# RTC.net
KiCad netlist of a schematic drawn in Altium Designer
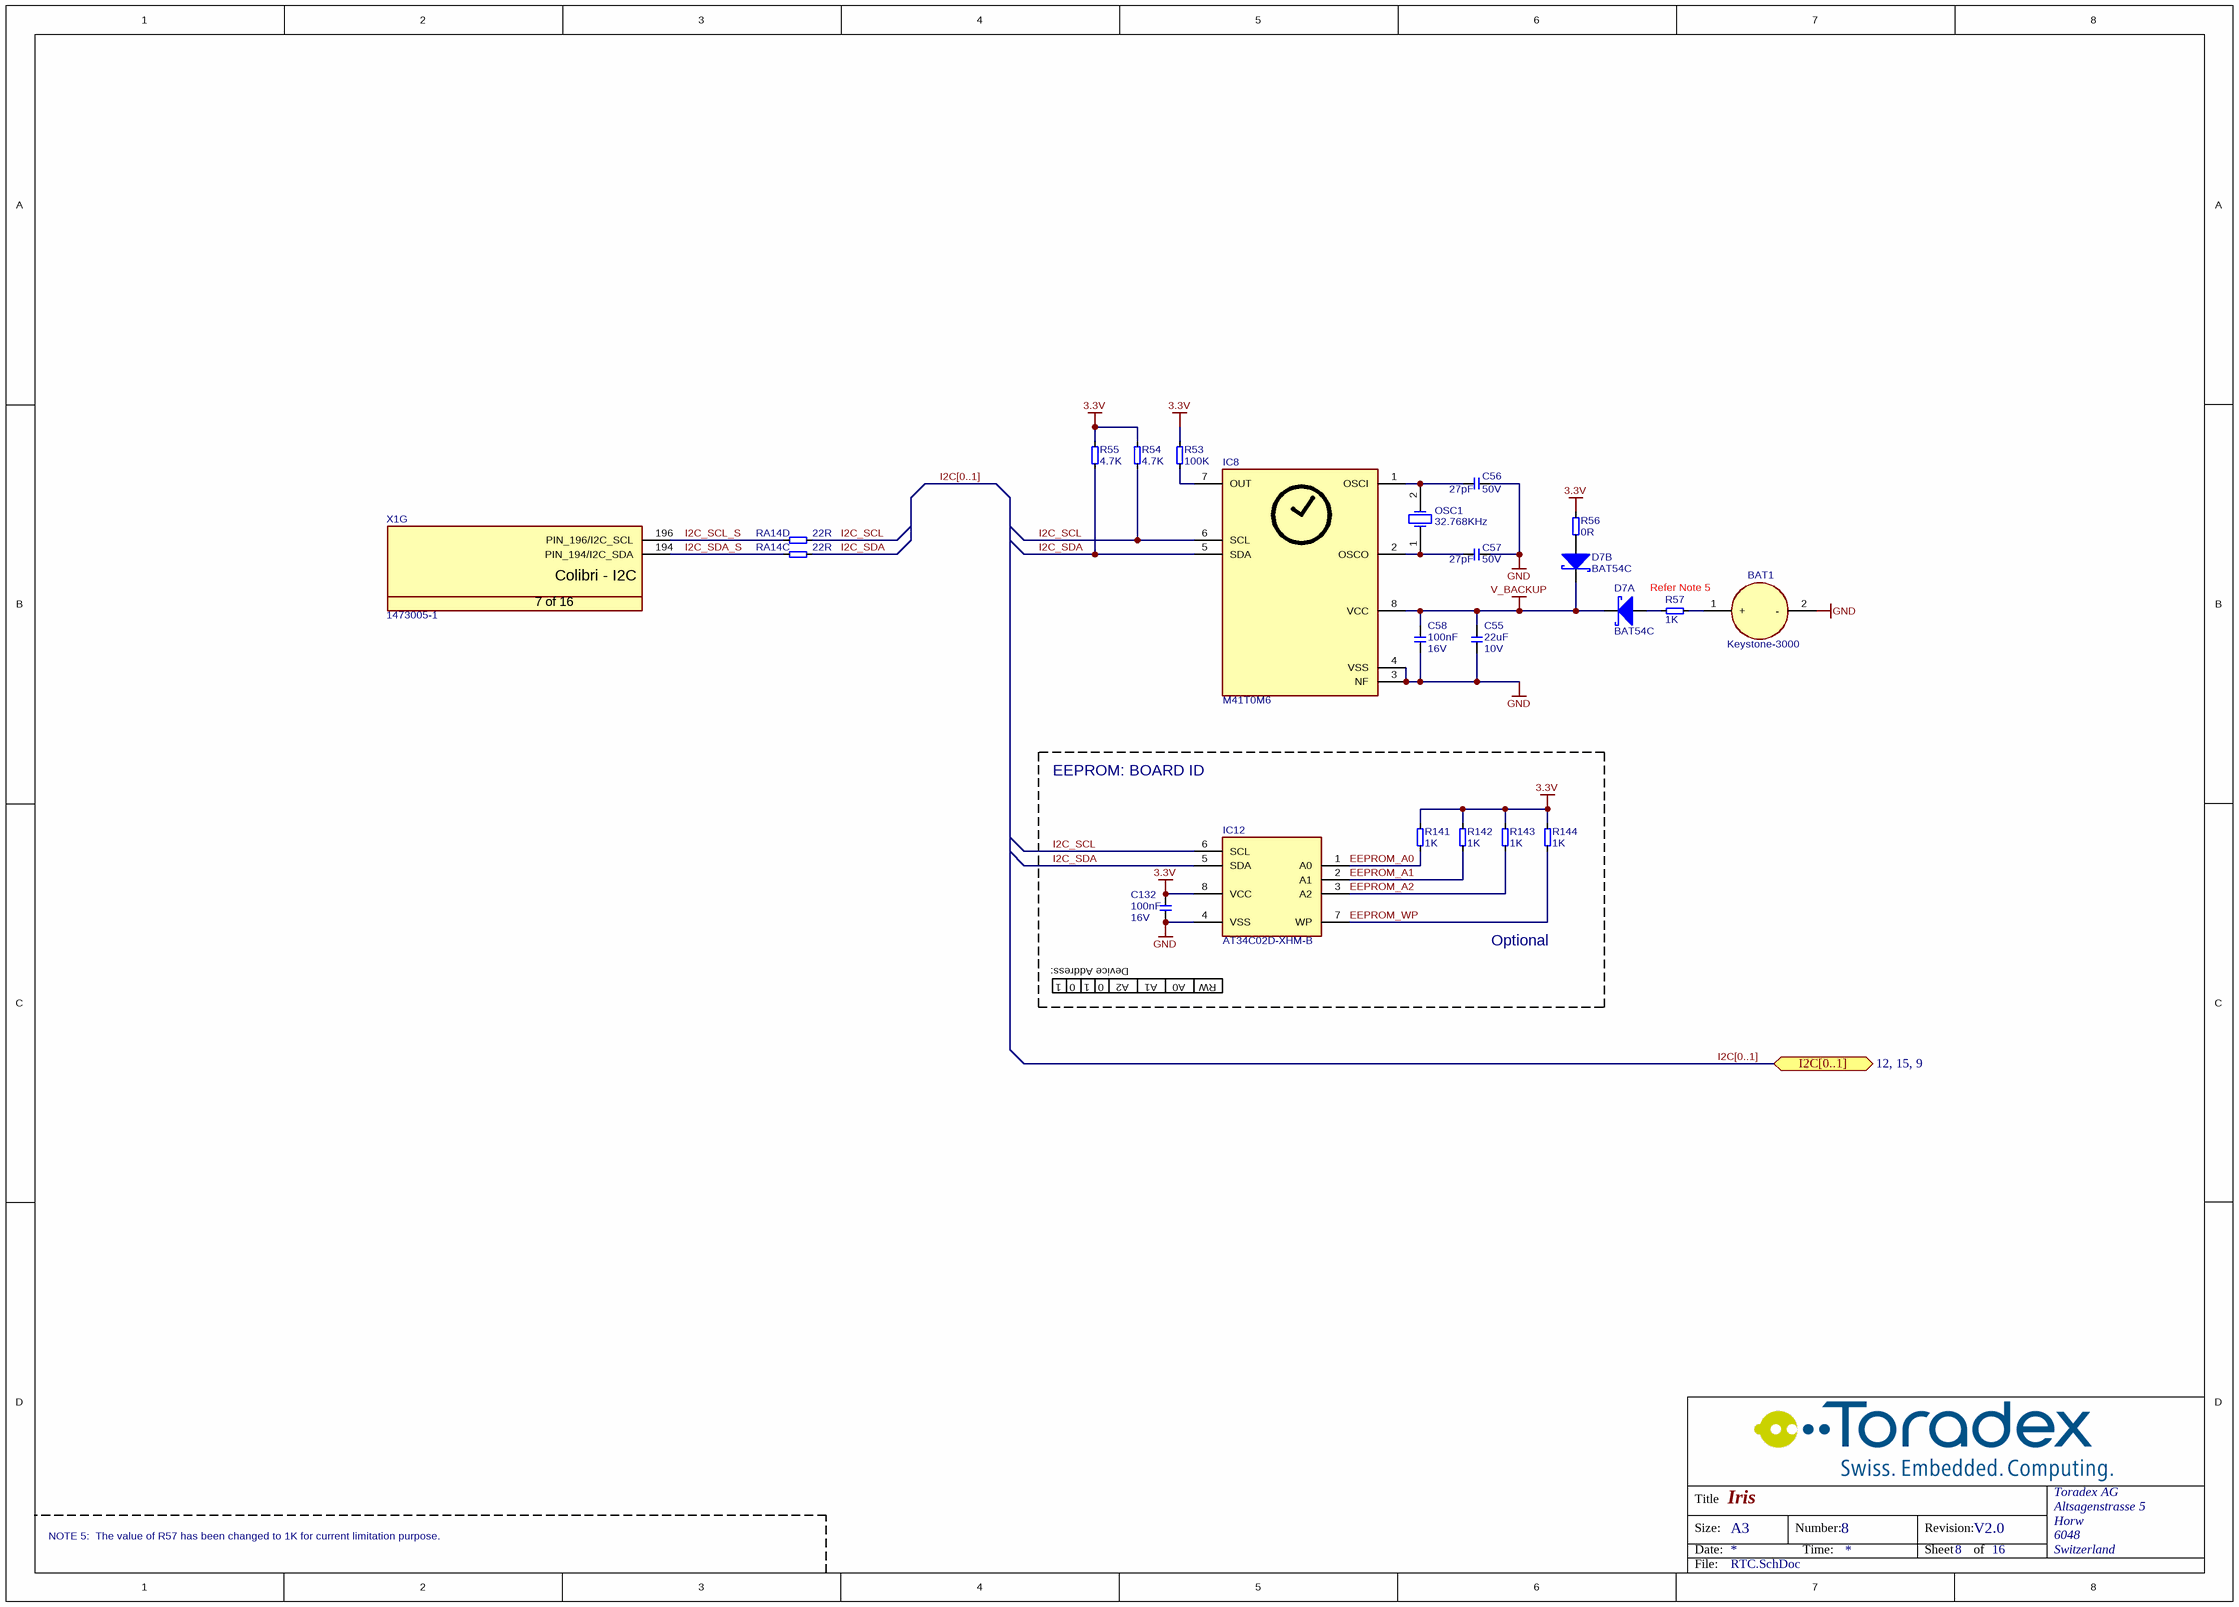
[diagram p0: RTC.SchDoc]

(export (version "E")
  (design (tool "Eeschema 10.0.6"))
  (components
    (comp (ref "BAT1")
      (value "Keystone-3000")
      (footprint "T_Keystone_3000")
      (description "Battery Holder")
      (fields (field (name "MANUFACTURER PART NO.") "3000"))
      (libsource (lib "Iris") (part "BAT-Keystone-3000"))
    )
    (comp (ref "C55")
      (value "22uF")
      (footprint "T_CAPC0805X125N")
      (description "Capacitor Ceramic X5R 22uF 10V 20% 0805")
      (fields (field (name "TOLERANCE") "20%") (field (name "RATING") "10V"))
      (libsource (lib "Iris") (part "C-X5R-22uF-10V-20%-0805"))
    )
    (comp (ref "C56")
      (value "27pF")
      (footprint "T_CAPC0603X33N")
      (description "Capacitor Ceramic NPO 27pF 50V 5% 0603")
      (fields (field (name "TOLERANCE") "5%") (field (name "RATING") "50V"))
      (libsource (lib "Iris") (part "C-NPO-27pF-50V-5%-0603"))
    )
    (comp (ref "C57")
      (value "27pF")
      (footprint "T_CAPC0603X33N")
      (description "Capacitor Ceramic NPO 27pF 50V 5% 0603")
      (fields (field (name "TOLERANCE") "5%") (field (name "RATING") "50V"))
      (libsource (lib "Iris") (part "C-NPO-27pF-50V-5%-0603"))
    )
    (comp (ref "C58")
      (value "100nF")
      (footprint "CAPC1005X60N")
      (description "Capacitor Ceramic X7R 100nF 16V 10% 0402")
      (fields (field (name "TOLERANCE") "10%") (field (name "RATING") "16V"))
      (libsource (lib "Iris") (part "C-X7R-100nF-16V-10%-0402"))
    )
    (comp (ref "C132")
      (value "100nF")
      (footprint "CAPC1005X60N")
      (description "Capacitor Ceramic X7R 100nF 16V 10% 0402")
      (fields (field (name "TOLERANCE") "10%") (field (name "RATING") "16V"))
      (libsource (lib "Iris") (part "C-X7R-100nF-16V-10%-0402"))
    )
    (comp (ref "D7")
      (value "BAT54C")
      (footprint "SOT95P230X110-3N")
      (description "BAT54C Schottky Diode")
      (fields (field (name "MANUFACTURER PART NO.") "BAT54C"))
      (libsource (lib "Iris") (part "D-Philips-BAT54C-Schottky"))
    )
    (comp (ref "IC8")
      (value "M41T0M6")
      (footprint "SOIC127P600X173-8N")
      (description "RTC M41T0M6")
      (fields (field (name "MANUFACTURER PART NO.") "M41T0M6"))
      (libsource (lib "Iris") (part "IC-ST-M41T0M6"))
    )
    (comp (ref "IC12")
      (value "AT34C02D-XHM-B")
      (footprint "TSOP65P650X120-8M")
      (description "EEPROM, 2Kbit (256 x 8), TSSOP-8 package")
      (fields (field (name "MANUFACTURER PART NO.") "AT34C02D-XHM-B"))
      (libsource (lib "Iris") (part "IC-Microchip-AT34C02D-XHM-B"))
    )
    (comp (ref "OSC1")
      (value "32.768KHz")
      (footprint "T_MC_CC4V-T1A")
      (description "Quartz 32.768kHz")
      (fields (field (name "TOLERANCE") "30ppm") (field (name "MANUFACTURER PART NO.") "CC4V-T1A"))
      (libsource (lib "Iris") (part "OSC-MC-CC4V-T1A-32.768KHz-30ppm-5x1.9mm"))
    )
    (comp (ref "R53")
      (value "100K")
      (footprint "T_RESC0603X30N")
      (description "Resistor 100 Kohm 63mW 5% 0603")
      (fields (field (name "TOLERANCE") "5%"))
      (libsource (lib "Iris") (part "R-100KR-63mW-5%-0603"))
    )
    (comp (ref "R54")
      (value "4.7K")
      (footprint "RESC1005X40N")
      (description "Resistor 4.7 Kohm 63mW 5% 0402")
      (fields (field (name "TOLERANCE") "5%"))
      (libsource (lib "Iris") (part "R-4.7kR-63mW-5%-0402"))
    )
    (comp (ref "R55")
      (value "4.7K")
      (footprint "RESC1005X40N")
      (description "Resistor 4.7 Kohm 63mW 5% 0402")
      (fields (field (name "TOLERANCE") "5%"))
      (libsource (lib "Iris") (part "R-4.7kR-63mW-5%-0402"))
    )
    (comp (ref "R56")
      (value "0R")
      (footprint "T_RESC0603X30N")
      (description "Resistor 0 ohm 63mW 5% 0603")
      (fields (field (name "TOLERANCE") "5%"))
      (libsource (lib "Iris") (part "R-0R-63mW-5%-0603"))
    )
    (comp (ref "R57")
      (value "1K")
      (footprint "RESC1005X40N")
      (description "Resistor 1 Kohm 63mW 5% 0402")
      (fields (field (name "TOLERANCE") "5%"))
      (libsource (lib "Iris") (part "R-1KR-63mW-5%-0402"))
    )
    (comp (ref "R141")
      (value "1K")
      (footprint "T_RESC0603X30N")
      (description "Resistor 1 Kohm 63mW 5% 0603")
      (fields (field (name "TOLERANCE") "5%"))
      (libsource (lib "Iris") (part "R-1KR-63mW-5%-0603"))
    )
    (comp (ref "R142")
      (value "1K")
      (footprint "T_RESC0603X30N")
      (description "Resistor 1 Kohm 63mW 5% 0603")
      (fields (field (name "TOLERANCE") "5%"))
      (libsource (lib "Iris") (part "R-1KR-63mW-5%-0603"))
    )
    (comp (ref "R143")
      (value "1K")
      (footprint "T_RESC0603X30N")
      (description "Resistor 1 Kohm 63mW 5% 0603")
      (fields (field (name "TOLERANCE") "5%"))
      (libsource (lib "Iris") (part "R-1KR-63mW-5%-0603"))
    )
    (comp (ref "R144")
      (value "1K")
      (footprint "T_RESC0603X30N")
      (description "Resistor 1 Kohm 63mW 5% 0603")
      (fields (field (name "TOLERANCE") "5%"))
      (libsource (lib "Iris") (part "R-1KR-63mW-5%-0603"))
    )
    (comp (ref "RA14")
      (value "22R")
      (footprint "T_Resistor_Array_X4")
      (description "Resistor Array 22 R 63mW 5% 1206")
      (fields (field (name "TOLERANCE") "5%"))
      (libsource (lib "Iris") (part "RA-22R-63mW-5%-1206-div"))
    )
    (comp (ref "X1")
      (value "1473005-1")
      (footprint "T_Tyco_1473005-1")
      (description "SODIMM Connector")
      (fields (field (name "MANUFACTURER PART NO.") "1473005-1"))
      (libsource (lib "Iris") (part "CON-Tyco-1473005-1-200-0.6mm"))
    )
  )
  (nets
    (net (code "3") (name "/EEPROM_A0") (class "Default")
      (node (ref "IC12") (pin "1") (pinfunction "A0_1") (pintype "passive"))
      (node (ref "R141") (pin "1") (pinfunction "1_1") (pintype "passive"))
    )
    (net (code "4") (name "/EEPROM_A1") (class "Default")
      (node (ref "IC12") (pin "2") (pinfunction "A1_2") (pintype "passive"))
      (node (ref "R142") (pin "1") (pinfunction "1_1") (pintype "passive"))
    )
    (net (code "5") (name "/EEPROM_A2") (class "Default")
      (node (ref "IC12") (pin "3") (pinfunction "A2_3") (pintype "passive"))
      (node (ref "R143") (pin "1") (pinfunction "1_1") (pintype "passive"))
    )
    (net (code "6") (name "/EEPROM_WP") (class "Default")
      (node (ref "IC12") (pin "7") (pinfunction "WP_7") (pintype "passive"))
      (node (ref "R144") (pin "1") (pinfunction "1_1") (pintype "passive"))
    )
    (net (code "8") (name "/I2C_SCL") (class "Default")
      (node (ref "IC12") (pin "6") (pinfunction "SCL_6") (pintype "passive"))
      (node (ref "IC8") (pin "6") (pinfunction "SCL_6") (pintype "passive"))
      (node (ref "R54") (pin "1") (pinfunction "1_1") (pintype "passive"))
      (node (ref "RA14") (pin "8") (pinfunction "8_8") (pintype "passive"))
    )
    (net (code "9") (name "/I2C_SCL_S") (class "Default")
      (node (ref "RA14") (pin "4") (pinfunction "4_4") (pintype "passive"))
      (node (ref "X1") (pin "196") (pinfunction "PIN_196/I2C_SCL_196") (pintype "passive"))
    )
    (net (code "10") (name "/I2C_SDA") (class "Default")
      (node (ref "IC12") (pin "5") (pinfunction "SDA_5") (pintype "passive"))
      (node (ref "IC8") (pin "5") (pinfunction "SDA_5") (pintype "passive"))
      (node (ref "R55") (pin "1") (pinfunction "1_1") (pintype "passive"))
      (node (ref "RA14") (pin "7") (pinfunction "7_7") (pintype "passive"))
    )
    (net (code "11") (name "/I2C_SDA_S") (class "Default")
      (node (ref "RA14") (pin "3") (pinfunction "3_3") (pintype "passive"))
      (node (ref "X1") (pin "194") (pinfunction "PIN_194/I2C_SDA_194") (pintype "passive"))
    )
    (net (code "12") (name "3.3V") (class "Default")
      (node (ref "C132") (pin "2") (pinfunction "2_2") (pintype "passive"))
      (node (ref "IC12") (pin "8") (pinfunction "VCC_8") (pintype "passive"))
      (node (ref "R141") (pin "2") (pinfunction "2_2") (pintype "passive"))
      (node (ref "R142") (pin "2") (pinfunction "2_2") (pintype "passive"))
      (node (ref "R143") (pin "2") (pinfunction "2_2") (pintype "passive"))
      (node (ref "R144") (pin "2") (pinfunction "2_2") (pintype "passive"))
      (node (ref "R53") (pin "2") (pinfunction "2_2") (pintype "passive"))
      (node (ref "R54") (pin "2") (pinfunction "2_2") (pintype "passive"))
      (node (ref "R55") (pin "2") (pinfunction "2_2") (pintype "passive"))
      (node (ref "R56") (pin "2") (pinfunction "2_2") (pintype "passive"))
    )
    (net (code "13") (name "GND") (class "Default")
      (node (ref "BAT1") (pin "2") (pinfunction "-_2") (pintype "passive"))
      (node (ref "C132") (pin "1") (pinfunction "1_1") (pintype "passive"))
      (node (ref "C55") (pin "1") (pinfunction "1_1") (pintype "passive"))
      (node (ref "C56") (pin "1") (pinfunction "1_1") (pintype "passive"))
      (node (ref "C57") (pin "1") (pinfunction "1_1") (pintype "passive"))
      (node (ref "C58") (pin "1") (pinfunction "1_1") (pintype "passive"))
      (node (ref "IC12") (pin "4") (pinfunction "VSS_4") (pintype "passive"))
      (node (ref "IC8") (pin "3") (pinfunction "NF_3") (pintype "passive"))
      (node (ref "IC8") (pin "4") (pinfunction "VSS_4") (pintype "passive"))
    )
    (net (code "14") (name "Net-(BAT1-+)") (class "Default")
      (node (ref "BAT1") (pin "1") (pinfunction "+_1") (pintype "passive"))
      (node (ref "R57") (pin "1") (pinfunction "1_1") (pintype "passive"))
    )
    (net (code "15") (name "Net-(D7-Pad1)") (class "Default")
      (node (ref "D7") (pin "1") (pinfunction "1_1") (pintype "passive"))
      (node (ref "R57") (pin "2") (pinfunction "2_2") (pintype "passive"))
    )
    (net (code "16") (name "Net-(D7-Pad2)") (class "Default")
      (node (ref "D7") (pin "2") (pinfunction "2_2") (pintype "passive"))
      (node (ref "R56") (pin "1") (pinfunction "1_1") (pintype "passive"))
    )
    (net (code "17") (name "Net-(IC8-OSCI)") (class "Default")
      (node (ref "C56") (pin "2") (pinfunction "2_2") (pintype "passive"))
      (node (ref "IC8") (pin "1") (pinfunction "OSCI_1") (pintype "passive"))
      (node (ref "OSC1") (pin "2") (pinfunction "OSC2_2") (pintype "passive"))
    )
    (net (code "18") (name "Net-(IC8-OSCO)") (class "Default")
      (node (ref "C57") (pin "2") (pinfunction "2_2") (pintype "passive"))
      (node (ref "IC8") (pin "2") (pinfunction "OSCO_2") (pintype "passive"))
      (node (ref "OSC1") (pin "1") (pinfunction "OSC1_1") (pintype "passive"))
    )
    (net (code "19") (name "Net-(IC8-OUT)") (class "Default")
      (node (ref "IC8") (pin "7") (pinfunction "OUT_7") (pintype "passive"))
      (node (ref "R53") (pin "1") (pinfunction "1_1") (pintype "passive"))
    )
    (net (code "20") (name "V_BACKUP") (class "Default")
      (node (ref "C55") (pin "2") (pinfunction "2_2") (pintype "passive"))
      (node (ref "C58") (pin "2") (pinfunction "2_2") (pintype "passive"))
      (node (ref "D7") (pin "3") (pinfunction "3_3") (pintype "passive"))
      (node (ref "IC8") (pin "8") (pinfunction "VCC_8") (pintype "passive"))
    )
  )
)
